# Regulator_cct.net
KiCad netlist of a schematic drawn in Altium Designer
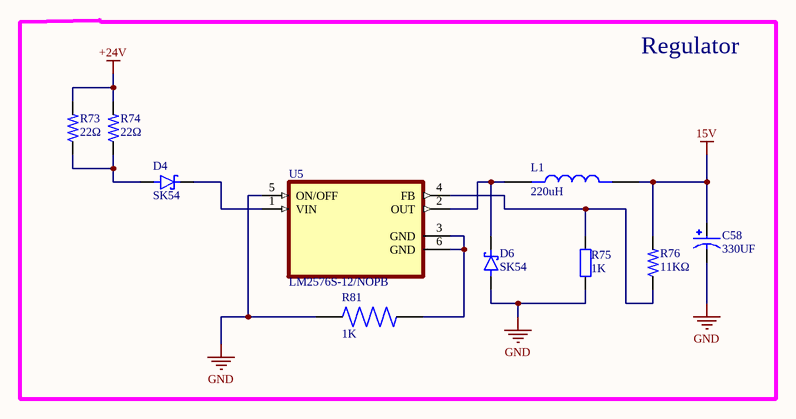
[diagram p0: Regulator_cct.SchDoc]

(export (version "E")
  (design (tool "Eeschema 10.0.6"))
  (components
    (comp (ref "C58")
      (value "330UF")
      (footprint "CAP_EEETC1C331V")
      (description "CAP ALUM 330UF 20% 16V SMD")
      (fields (field (name "MP") "EEE-TC1C331V") (field (name "MF") "Panasonic Electronic Components"))
      (libsource (lib "PROJE") (part "CAP 330UF SMD"))
    )
    (comp (ref "D4")
      (value "SK54")
      (footprint "DIOM7959X265N")
      (description "Diode Schottky 40V 5A Surface Mount DO-214AA (SMB)")
      (fields (field (name "MP") "MBRS320T3G") (field (name "MF") "ON Semiconductor"))
      (libsource (lib "PROJE") (part "SK54"))
    )
    (comp (ref "D6")
      (value "SK54")
      (footprint "DIOM7959X265N")
      (description "Diode Schottky 40V 5A Surface Mount DO-214AA (SMB)")
      (fields (field (name "MP") "MBRS320T3G") (field (name "MF") "ON Semiconductor"))
      (libsource (lib "PROJE") (part "SK54"))
    )
    (comp (ref "L1")
      (value "220uH")
      (footprint "IND_MDH12577C-101MA=P3")
      (description "Inductor Power Shielded Wirewound 220uH 20% 100KHz Ferrite 1.1A 0.325Ohm DCR 5049 Automotive T/R")
      (fields (field (name "MP") "MDH12577C-101MA=P3"))
      (libsource (lib "PROJE") (part "220uH Inductor SMD"))
    )
    (comp (ref "R73") (value "22Ω") (footprint "R-2512R") (libsource (lib "PROJE") (part "RES 22Ω 2512")))
    (comp (ref "R74") (value "22Ω") (footprint "R-2512R") (libsource (lib "PROJE") (part "RES 22Ω 2512")))
    (comp (ref "R75")
      (value "RES SMD 1K OHM 1% 1/8W 0805")
      (footprint "R-0805W")
      (description "1 kOhms ±1% 0.125W, 1/8W Chip Resistor 0805 (2012 Metric) Moisture Resistant Thick Film")
      (fields (field (name "DEGER") "1K"))
      (libsource (lib "PROJE") (part "1K 0805"))
    )
    (comp (ref "R76")
      (value "11KΩ")
      (footprint "R-0805R")
      (description "THICK FILM RESISTOR, 11KOHM, 125mW, 5%")
      (fields (field (name "MP") "CRCW080511K0JNEA"))
      (libsource (lib "PROJE") (part "RES 11KΩ SMD"))
    )
    (comp (ref "R81")
      (value "1K")
      (footprint "RESC6332X65N")
      (description "Fixed Resistor CRGP 2512 1K0 1%")
      (fields (field (name "MF") "TE Connectivity") (field (name "MP") "CRGP2512F1K0"))
      (libsource (lib "PROJE") (part "RES 1K 2512"))
    )
    (comp (ref "U5")
      (value "LM2576S-12/NOPB")
      (footprint "VREG_TPS79625KTTR")
      (description "SIMPLE SWITCHER&reg; 40V, 3A Low Component Count Step-Down Regulator 5-DDPAK/TO-263 -40 to 125")
      (fields
        (field (name "MF") "Texas Instruments")
        (field (name "BUYPART") "https://www.snapeda.com/parts/LM2576S-12/NOPB/Texas%20Instruments/view-part/470772/?ref=eda")
      )
      (libsource (lib "PROJE") (part "LM2576S-12/NOPB"))
    )
  )
  (nets
    (net (code "1") (name "+24V") (class "Default")
      (node (ref "R73") (pin "2") (pinfunction "2_2") (pintype "passive"))
      (node (ref "R74") (pin "2") (pinfunction "2_2") (pintype "passive"))
    )
    (net (code "2") (name "15V") (class "Default")
      (node (ref "C58") (pin "1") (pinfunction "1_1") (pintype "passive"))
      (node (ref "L1") (pin "2") (pinfunction "2_2") (pintype "passive"))
      (node (ref "R76") (pin "2") (pinfunction "2_2") (pintype "passive"))
    )
    (net (code "3") (name "GND") (class "Default")
      (node (ref "C58") (pin "2") (pinfunction "2_2") (pintype "passive"))
      (node (ref "D6") (pin "A") (pinfunction "A_A") (pintype "passive"))
      (node (ref "R75") (pin "1") (pinfunction "1_1") (pintype "passive"))
      (node (ref "R81") (pin "1") (pinfunction "1_1") (pintype "passive"))
      (node (ref "U5") (pin "5") (pinfunction "ON/OFF_5") (pintype "input"))
    )
    (net (code "4") (name "Net-(D4-K)") (class "Default")
      (node (ref "D4") (pin "C") (pinfunction "K_C") (pintype "passive"))
      (node (ref "U5") (pin "1") (pinfunction "VIN_1") (pintype "input"))
    )
    (net (code "5") (name "Net-(D4-PadA)") (class "Default")
      (node (ref "D4") (pin "A") (pinfunction "A_A") (pintype "passive"))
      (node (ref "R73") (pin "1") (pinfunction "1_1") (pintype "passive"))
      (node (ref "R74") (pin "1") (pinfunction "1_1") (pintype "passive"))
    )
    (net (code "6") (name "Net-(D6-K)") (class "Default")
      (node (ref "D6") (pin "C") (pinfunction "K_C") (pintype "passive"))
      (node (ref "L1") (pin "1") (pinfunction "1_1") (pintype "passive"))
      (node (ref "U5") (pin "2") (pinfunction "OUT_2") (pintype "output"))
    )
    (net (code "7") (name "Net-(R81-Pad2)") (class "Default")
      (node (ref "R81") (pin "2") (pinfunction "2_2") (pintype "passive"))
      (node (ref "U5") (pin "3") (pinfunction "GND_3") (pintype "power_in"))
      (node (ref "U5") (pin "6") (pinfunction "GND_6") (pintype "power_in"))
    )
    (net (code "8") (name "Net-(U5-FB)") (class "Default")
      (node (ref "R75") (pin "2") (pinfunction "2_2") (pintype "passive"))
      (node (ref "R76") (pin "1") (pinfunction "1_1") (pintype "passive"))
      (node (ref "U5") (pin "4") (pinfunction "FB_4") (pintype "output"))
    )
  )
)
